# connector_a.net
KiCad netlist of a schematic drawn in Altium Designer
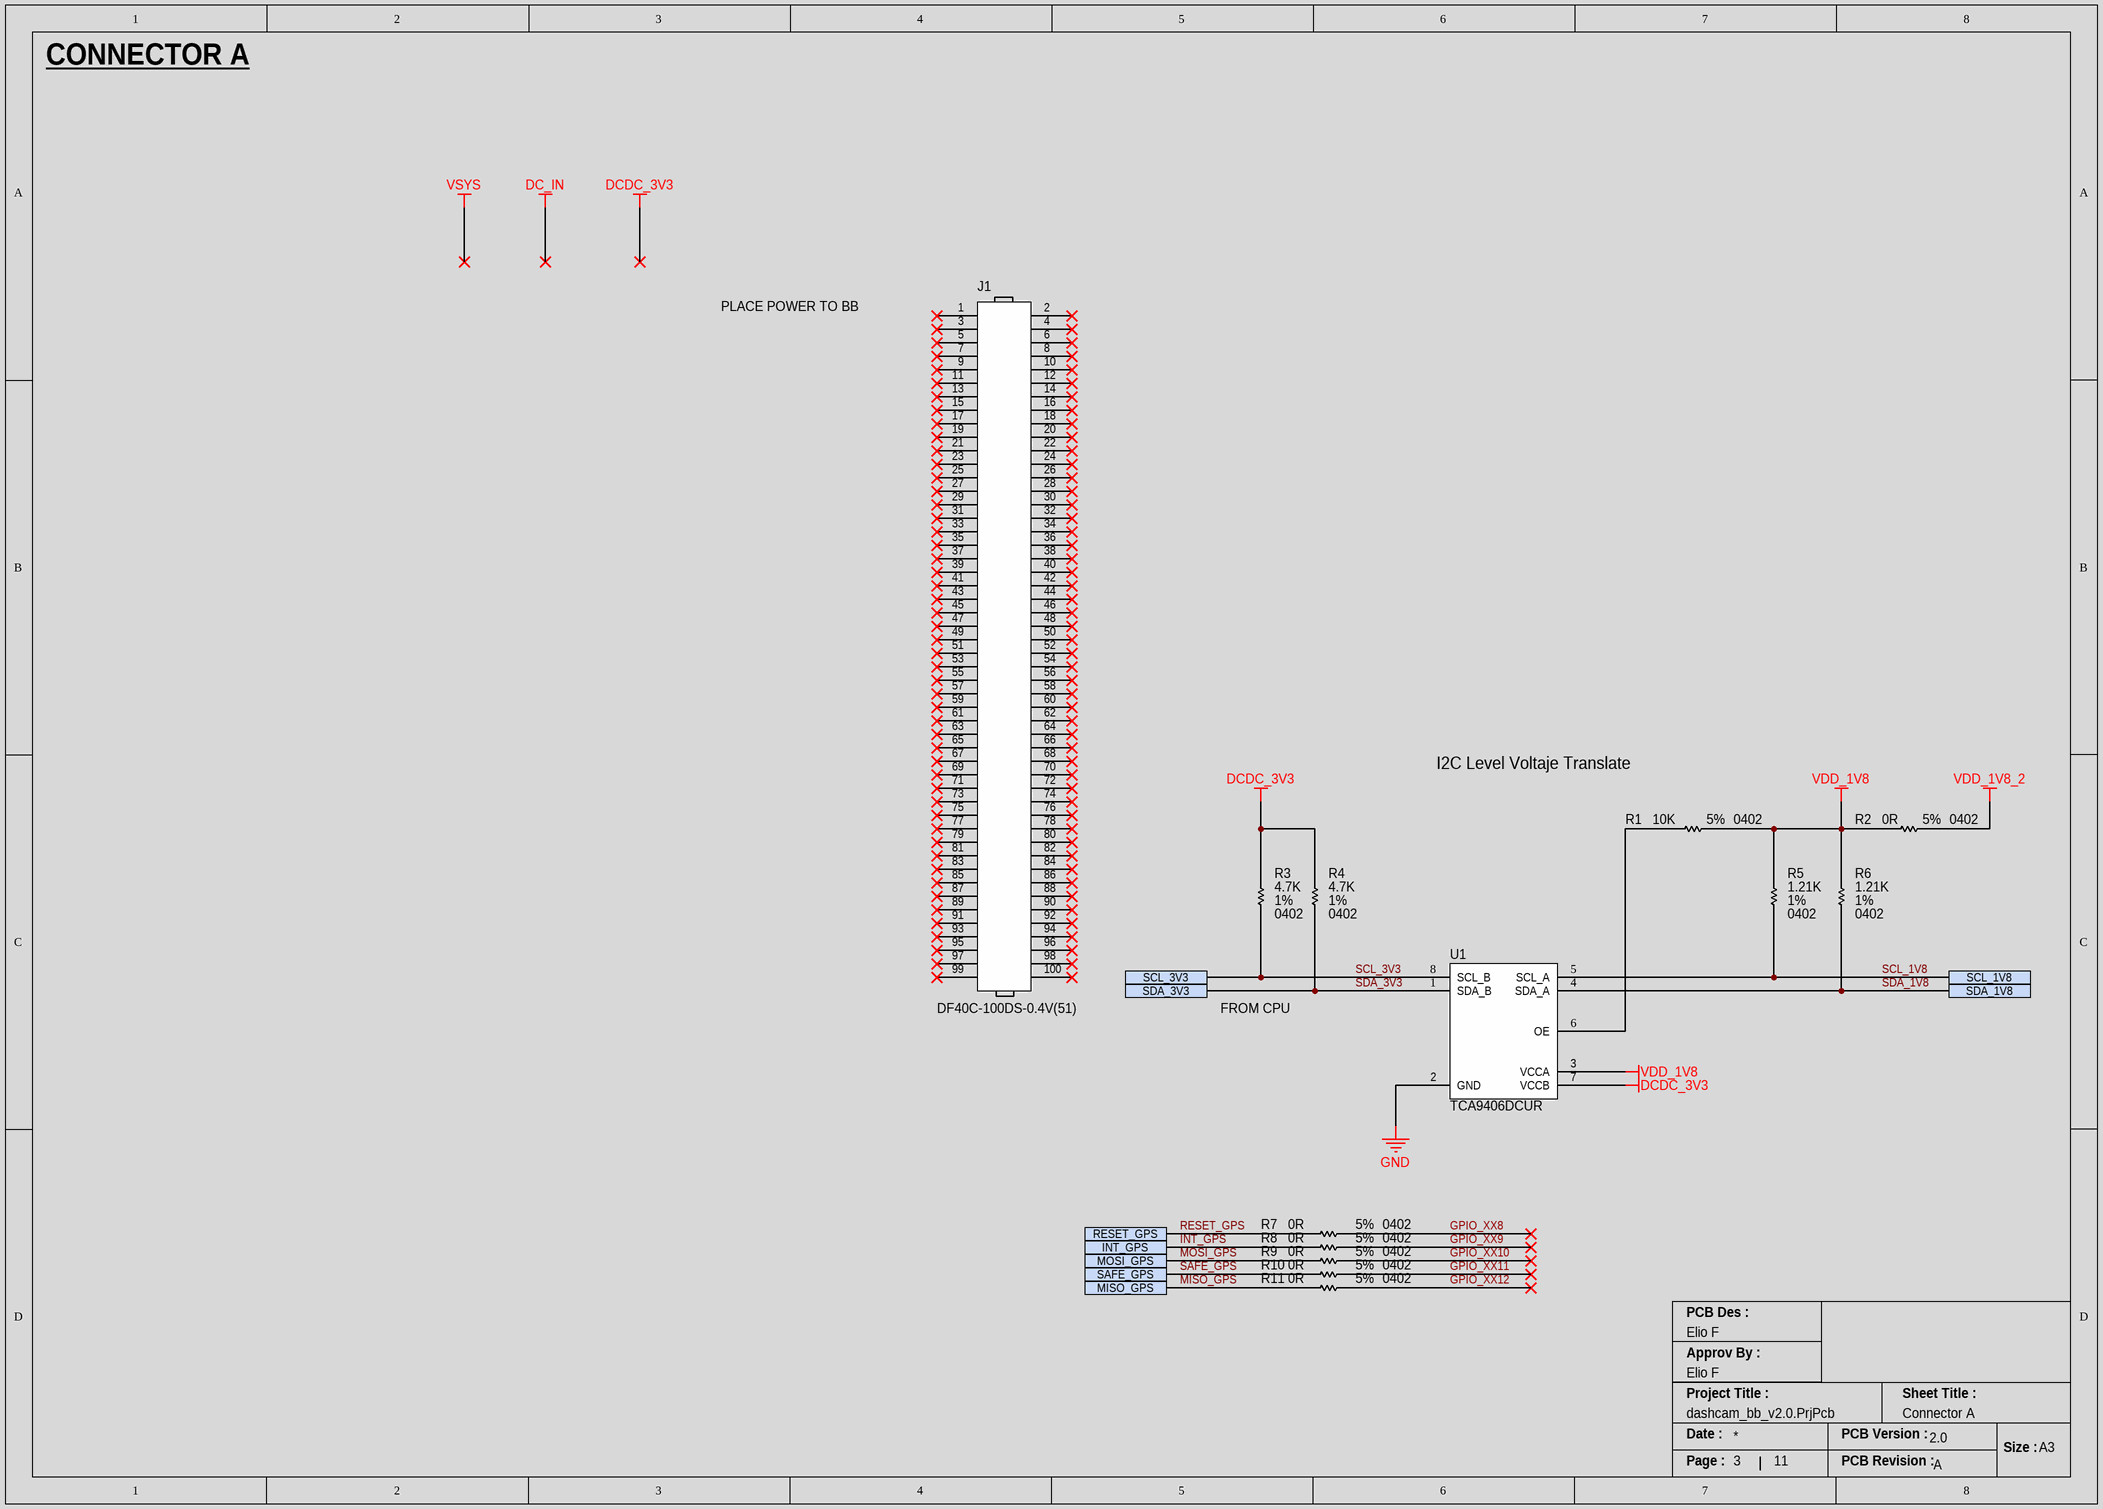
[diagram p0: connector_a.SchDoc]

(export (version "E")
  (design (tool "Eeschema 10.0.6"))
  (components
    (comp (ref "J1")
      (value "DF40C-100DS-0.4V(51)")
      (footprint "CONN_B2B_HIROSE_DF40C-100DS-0.4V(51)")
      (description "Board-to-Board Connector with 0.4-mm Pitch, 1.5 - 4.0-mm Height - DF40 Series (HIROSE ELECTRIC)")
      (fields (field (name "MANUFACTURER") "Hirose"))
      (libsource (lib "Electronic Devices_LIB") (part "CONN_B2B_100P_RE_DF40C-100DS-0.4V(51)"))
    )
    (comp (ref "R1")
      (value "ERJ-2GEJ103X")
      (footprint "RES_0402_RESC1005X04N")
      (description "Res Thick Film 0402 10K Ohm 5% 1/10W ±200ppm/°C Molded SMD Punched Carrier T/R")
      (fields
        (field (name "MANUFACTURER") "Panasonic")
        (field (name "TOLERANCE") "5%")
        (field (name "RESISTANCE") "10K")
        (field (name "CASE/PACKAGE") "0402")
      )
      (libsource (lib "Electronic Devices_LIB") (part "RES_10K_5%_100mW_0402"))
    )
    (comp (ref "R2")
      (value "ERJ-2GE0R00X")
      (footprint "RES_0402_RESC1005X04N")
      (description "SMD Chip Resistor, Jumper, 0 ohm, 100 mW, 0402 [1005 Metric], Thick Film, General Purpose")
      (fields
        (field (name "MANUFACTURER") "Panasonic")
        (field (name "CASE CODE (IMPERIAL)") "0402")
        (field (name "TOLERANCE") "5%")
        (field (name "RESISTANCE") "0R")
      )
      (libsource (lib "Electronic Devices_LIB") (part "RES_0R_5%_100mW_0402"))
    )
    (comp (ref "R3")
      (value "ERJ-2RKF4701X")
      (footprint "RES_0402_RESC1005X04N")
      (description "Res Thick Film 0402 4.7K Ohm 1% 0.1W ±100ppm/°C Molded SMD Punched Carrier T/R")
      (fields
        (field (name "MANUFACTURER") "Panasonic")
        (field (name "TOLERANCE") "1%")
        (field (name "CASE CODE (IMPERIAL)") "0402")
        (field (name "RESISTANCE") "4.7K")
      )
      (libsource (lib "Electronic Devices_LIB") (part "RES_4.7K_1%_100mW_0402"))
    )
    (comp (ref "R4")
      (value "ERJ-2RKF4701X")
      (footprint "RES_0402_RESC1005X04N")
      (description "Res Thick Film 0402 4.7K Ohm 1% 0.1W ±100ppm/°C Molded SMD Punched Carrier T/R")
      (fields
        (field (name "MANUFACTURER") "Panasonic")
        (field (name "TOLERANCE") "1%")
        (field (name "CASE CODE (IMPERIAL)") "0402")
        (field (name "RESISTANCE") "4.7K")
      )
      (libsource (lib "Electronic Devices_LIB") (part "RES_4.7K_1%_100mW_0402"))
    )
    (comp (ref "R5")
      (value "CRCW04021K21FKED")
      (footprint "RES_0402_RESC1005X04N")
      (description "Res Thick Film 0402 1.21K Ohm 1% 1/16W ±100ppm/°C Molded SMD Paper T/R")
      (fields
        (field (name "MANUFACTURER") "Vishay")
        (field (name "TOLERANCE") "1%")
        (field (name "RESISTANCE") "1.21K")
        (field (name "CASE/PACKAGE") "0402")
      )
      (libsource (lib "Electronic Devices_LIB") (part "RES_1.21K_1%_63mW_0402"))
    )
    (comp (ref "R6")
      (value "CRCW04021K21FKED")
      (footprint "RES_0402_RESC1005X04N")
      (description "Res Thick Film 0402 1.21K Ohm 1% 1/16W ±100ppm/°C Molded SMD Paper T/R")
      (fields
        (field (name "MANUFACTURER") "Vishay")
        (field (name "TOLERANCE") "1%")
        (field (name "RESISTANCE") "1.21K")
        (field (name "CASE/PACKAGE") "0402")
      )
      (libsource (lib "Electronic Devices_LIB") (part "RES_1.21K_1%_63mW_0402"))
    )
    (comp (ref "R7")
      (value "ERJ-2GE0R00X")
      (footprint "RES_0402_RESC1005X04N")
      (description "SMD Chip Resistor, Jumper, 0 ohm, 100 mW, 0402 [1005 Metric], Thick Film, General Purpose")
      (fields
        (field (name "MANUFACTURER") "Panasonic")
        (field (name "CASE CODE (IMPERIAL)") "0402")
        (field (name "TOLERANCE") "5%")
        (field (name "RESISTANCE") "0R")
      )
      (libsource (lib "Electronic Devices_LIB") (part "RES_0R_5%_100mW_0402"))
    )
    (comp (ref "R8")
      (value "ERJ-2GE0R00X")
      (footprint "RES_0402_RESC1005X04N")
      (description "SMD Chip Resistor, Jumper, 0 ohm, 100 mW, 0402 [1005 Metric], Thick Film, General Purpose")
      (fields
        (field (name "MANUFACTURER") "Panasonic")
        (field (name "CASE CODE (IMPERIAL)") "0402")
        (field (name "TOLERANCE") "5%")
        (field (name "RESISTANCE") "0R")
      )
      (libsource (lib "Electronic Devices_LIB") (part "RES_0R_5%_100mW_0402"))
    )
    (comp (ref "R9")
      (value "ERJ-2GE0R00X")
      (footprint "RES_0402_RESC1005X04N")
      (description "SMD Chip Resistor, Jumper, 0 ohm, 100 mW, 0402 [1005 Metric], Thick Film, General Purpose")
      (fields
        (field (name "MANUFACTURER") "Panasonic")
        (field (name "CASE CODE (IMPERIAL)") "0402")
        (field (name "TOLERANCE") "5%")
        (field (name "RESISTANCE") "0R")
      )
      (libsource (lib "Electronic Devices_LIB") (part "RES_0R_5%_100mW_0402"))
    )
    (comp (ref "R10")
      (value "ERJ-2GE0R00X")
      (footprint "RES_0402_RESC1005X04N")
      (description "SMD Chip Resistor, Jumper, 0 ohm, 100 mW, 0402 [1005 Metric], Thick Film, General Purpose")
      (fields
        (field (name "MANUFACTURER") "Panasonic")
        (field (name "CASE CODE (IMPERIAL)") "0402")
        (field (name "TOLERANCE") "5%")
        (field (name "RESISTANCE") "0R")
      )
      (libsource (lib "Electronic Devices_LIB") (part "RES_0R_5%_100mW_0402"))
    )
    (comp (ref "R11")
      (value "ERJ-2GE0R00X")
      (footprint "RES_0402_RESC1005X04N")
      (description "SMD Chip Resistor, Jumper, 0 ohm, 100 mW, 0402 [1005 Metric], Thick Film, General Purpose")
      (fields
        (field (name "MANUFACTURER") "Panasonic")
        (field (name "CASE CODE (IMPERIAL)") "0402")
        (field (name "TOLERANCE") "5%")
        (field (name "RESISTANCE") "0R")
      )
      (libsource (lib "Electronic Devices_LIB") (part "RES_0R_5%_100mW_0402"))
    )
    (comp (ref "U1")
      (value "TCA9406DCUR")
      (footprint "IC_LEVEL_TRASLATOR_SOP50P310X90-8N")
      (description "Voltage Level Translator Bidirectional 1 Circuit 2 Channel 24Mbps US8")
      (fields (field (name "MANUFACTURER") "Texas Instruments"))
      (libsource (lib "Electronic Devices_LIB") (part "IC_LEVEL_TRASLATOR_TCA9406DCUR"))
    )
  )
  (nets
    (net (code "1") (name "/GPIO_XX8") (class "Default")
      (node (ref "R7") (pin "2") (pinfunction "2_2") (pintype "passive+no_connect"))
    )
    (net (code "2") (name "/GPIO_XX9") (class "Default")
      (node (ref "R8") (pin "2") (pinfunction "2_2") (pintype "passive+no_connect"))
    )
    (net (code "3") (name "/GPIO_XX10") (class "Default")
      (node (ref "R9") (pin "2") (pinfunction "2_2") (pintype "passive+no_connect"))
    )
    (net (code "4") (name "/GPIO_XX11") (class "Default")
      (node (ref "R10") (pin "2") (pinfunction "2_2") (pintype "passive+no_connect"))
    )
    (net (code "5") (name "/GPIO_XX12") (class "Default")
      (node (ref "R11") (pin "2") (pinfunction "2_2") (pintype "passive+no_connect"))
    )
    (net (code "6") (name "/INT_GPS") (class "Default")
      (node (ref "R8") (pin "1") (pinfunction "1_1") (pintype "passive"))
    )
    (net (code "7") (name "/MISO_GPS") (class "Default")
      (node (ref "R11") (pin "1") (pinfunction "1_1") (pintype "passive"))
    )
    (net (code "8") (name "/MOSI_GPS") (class "Default")
      (node (ref "R9") (pin "1") (pinfunction "1_1") (pintype "passive"))
    )
    (net (code "9") (name "/RESET_GPS") (class "Default")
      (node (ref "R7") (pin "1") (pinfunction "1_1") (pintype "passive"))
    )
    (net (code "10") (name "/SAFE_GPS") (class "Default")
      (node (ref "R10") (pin "1") (pinfunction "1_1") (pintype "passive"))
    )
    (net (code "11") (name "/SCL_1V8") (class "Default")
      (node (ref "R5") (pin "1") (pinfunction "1_1") (pintype "passive"))
      (node (ref "U1") (pin "5") (pinfunction "SCL_A_5") (pintype "passive"))
    )
    (net (code "12") (name "/SCL_3V3") (class "Default")
      (node (ref "R3") (pin "2") (pinfunction "2_2") (pintype "passive"))
      (node (ref "U1") (pin "8") (pinfunction "SCL_B_8") (pintype "passive"))
    )
    (net (code "13") (name "/SDA_1V8") (class "Default")
      (node (ref "R6") (pin "1") (pinfunction "1_1") (pintype "passive"))
      (node (ref "U1") (pin "4") (pinfunction "SDA_A_4") (pintype "passive"))
    )
    (net (code "14") (name "/SDA_3V3") (class "Default")
      (node (ref "R4") (pin "2") (pinfunction "2_2") (pintype "passive"))
      (node (ref "U1") (pin "1") (pinfunction "SDA_B_1") (pintype "passive"))
    )
    (net (code "15") (name "DCDC_3V3") (class "Default")
      (node (ref "R3") (pin "1") (pinfunction "1_1") (pintype "passive"))
      (node (ref "R4") (pin "1") (pinfunction "1_1") (pintype "passive"))
      (node (ref "U1") (pin "7") (pinfunction "VCCB_7") (pintype "power_in"))
    )
    (net (code "17") (name "GND") (class "Default")
      (node (ref "U1") (pin "2") (pinfunction "GND_2") (pintype "power_in"))
    )
    (net (code "18") (name "Net-(U1-OE)") (class "Default")
      (node (ref "R1") (pin "1") (pinfunction "1_1") (pintype "passive"))
      (node (ref "U1") (pin "6") (pinfunction "OE_6") (pintype "passive"))
    )
    (net (code "19") (name "VDD_1V8") (class "Default")
      (node (ref "R1") (pin "2") (pinfunction "2_2") (pintype "passive"))
      (node (ref "R2") (pin "1") (pinfunction "1_1") (pintype "passive"))
      (node (ref "R5") (pin "2") (pinfunction "2_2") (pintype "passive"))
      (node (ref "R6") (pin "2") (pinfunction "2_2") (pintype "passive"))
      (node (ref "U1") (pin "3") (pinfunction "VCCA_3") (pintype "power_in"))
    )
    (net (code "20") (name "VDD_1V8_2") (class "Default")
      (node (ref "R2") (pin "2") (pinfunction "2_2") (pintype "passive"))
    )
    (net (code "22") (name "unconnected-(J1-Pad1)") (class "Default")
      (node (ref "J1") (pin "1") (pinfunction "1_1") (pintype "passive+no_connect"))
    )
    (net (code "23") (name "unconnected-(J1-Pad2)") (class "Default")
      (node (ref "J1") (pin "2") (pinfunction "2_2") (pintype "passive+no_connect"))
    )
    (net (code "24") (name "unconnected-(J1-Pad3)") (class "Default")
      (node (ref "J1") (pin "3") (pinfunction "3_3") (pintype "passive+no_connect"))
    )
    (net (code "25") (name "unconnected-(J1-Pad4)") (class "Default")
      (node (ref "J1") (pin "4") (pinfunction "4_4") (pintype "passive+no_connect"))
    )
    (net (code "26") (name "unconnected-(J1-Pad5)") (class "Default")
      (node (ref "J1") (pin "5") (pinfunction "5_5") (pintype "passive+no_connect"))
    )
    (net (code "27") (name "unconnected-(J1-Pad6)") (class "Default")
      (node (ref "J1") (pin "6") (pinfunction "6_6") (pintype "passive+no_connect"))
    )
    (net (code "28") (name "unconnected-(J1-Pad7)") (class "Default")
      (node (ref "J1") (pin "7") (pinfunction "7_7") (pintype "passive+no_connect"))
    )
    (net (code "29") (name "unconnected-(J1-Pad8)") (class "Default")
      (node (ref "J1") (pin "8") (pinfunction "8_8") (pintype "passive+no_connect"))
    )
    (net (code "30") (name "unconnected-(J1-Pad9)") (class "Default")
      (node (ref "J1") (pin "9") (pinfunction "9_9") (pintype "passive+no_connect"))
    )
    (net (code "31") (name "unconnected-(J1-Pad10)") (class "Default")
      (node (ref "J1") (pin "10") (pinfunction "10_10") (pintype "passive+no_connect"))
    )
    (net (code "32") (name "unconnected-(J1-Pad11)") (class "Default")
      (node (ref "J1") (pin "11") (pinfunction "11_11") (pintype "passive+no_connect"))
    )
    (net (code "33") (name "unconnected-(J1-Pad12)") (class "Default")
      (node (ref "J1") (pin "12") (pinfunction "12_12") (pintype "passive+no_connect"))
    )
    (net (code "34") (name "unconnected-(J1-Pad13)") (class "Default")
      (node (ref "J1") (pin "13") (pinfunction "13_13") (pintype "passive+no_connect"))
    )
    (net (code "35") (name "unconnected-(J1-Pad14)") (class "Default")
      (node (ref "J1") (pin "14") (pinfunction "14_14") (pintype "passive+no_connect"))
    )
    (net (code "36") (name "unconnected-(J1-Pad15)") (class "Default")
      (node (ref "J1") (pin "15") (pinfunction "15_15") (pintype "passive+no_connect"))
    )
    (net (code "37") (name "unconnected-(J1-Pad16)") (class "Default")
      (node (ref "J1") (pin "16") (pinfunction "16_16") (pintype "passive+no_connect"))
    )
    (net (code "38") (name "unconnected-(J1-Pad17)") (class "Default")
      (node (ref "J1") (pin "17") (pinfunction "17_17") (pintype "passive+no_connect"))
    )
    (net (code "39") (name "unconnected-(J1-Pad18)") (class "Default")
      (node (ref "J1") (pin "18") (pinfunction "18_18") (pintype "passive+no_connect"))
    )
    (net (code "40") (name "unconnected-(J1-Pad19)") (class "Default")
      (node (ref "J1") (pin "19") (pinfunction "19_19") (pintype "passive+no_connect"))
    )
    (net (code "41") (name "unconnected-(J1-Pad20)") (class "Default")
      (node (ref "J1") (pin "20") (pinfunction "20_20") (pintype "passive+no_connect"))
    )
    (net (code "42") (name "unconnected-(J1-Pad21)") (class "Default")
      (node (ref "J1") (pin "21") (pinfunction "21_21") (pintype "passive+no_connect"))
    )
    (net (code "43") (name "unconnected-(J1-Pad22)") (class "Default")
      (node (ref "J1") (pin "22") (pinfunction "22_22") (pintype "passive+no_connect"))
    )
    (net (code "44") (name "unconnected-(J1-Pad23)") (class "Default")
      (node (ref "J1") (pin "23") (pinfunction "23_23") (pintype "passive+no_connect"))
    )
    (net (code "45") (name "unconnected-(J1-Pad24)") (class "Default")
      (node (ref "J1") (pin "24") (pinfunction "24_24") (pintype "passive+no_connect"))
    )
    (net (code "46") (name "unconnected-(J1-Pad25)") (class "Default")
      (node (ref "J1") (pin "25") (pinfunction "25_25") (pintype "passive+no_connect"))
    )
    (net (code "47") (name "unconnected-(J1-Pad26)") (class "Default")
      (node (ref "J1") (pin "26") (pinfunction "26_26") (pintype "passive+no_connect"))
    )
    (net (code "48") (name "unconnected-(J1-Pad27)") (class "Default")
      (node (ref "J1") (pin "27") (pinfunction "27_27") (pintype "passive+no_connect"))
    )
    (net (code "49") (name "unconnected-(J1-Pad28)") (class "Default")
      (node (ref "J1") (pin "28") (pinfunction "28_28") (pintype "passive+no_connect"))
    )
    (net (code "50") (name "unconnected-(J1-Pad29)") (class "Default")
      (node (ref "J1") (pin "29") (pinfunction "29_29") (pintype "passive+no_connect"))
    )
    (net (code "51") (name "unconnected-(J1-Pad30)") (class "Default")
      (node (ref "J1") (pin "30") (pinfunction "30_30") (pintype "passive+no_connect"))
    )
    (net (code "52") (name "unconnected-(J1-Pad31)") (class "Default")
      (node (ref "J1") (pin "31") (pinfunction "31_31") (pintype "passive+no_connect"))
    )
    (net (code "53") (name "unconnected-(J1-Pad32)") (class "Default")
      (node (ref "J1") (pin "32") (pinfunction "32_32") (pintype "passive+no_connect"))
    )
    (net (code "54") (name "unconnected-(J1-Pad33)") (class "Default")
      (node (ref "J1") (pin "33") (pinfunction "33_33") (pintype "passive+no_connect"))
    )
    (net (code "55") (name "unconnected-(J1-Pad34)") (class "Default")
      (node (ref "J1") (pin "34") (pinfunction "34_34") (pintype "passive+no_connect"))
    )
    (net (code "56") (name "unconnected-(J1-Pad35)") (class "Default")
      (node (ref "J1") (pin "35") (pinfunction "35_35") (pintype "passive+no_connect"))
    )
    (net (code "57") (name "unconnected-(J1-Pad36)") (class "Default")
      (node (ref "J1") (pin "36") (pinfunction "36_36") (pintype "passive+no_connect"))
    )
    (net (code "58") (name "unconnected-(J1-Pad37)") (class "Default")
      (node (ref "J1") (pin "37") (pinfunction "37_37") (pintype "passive+no_connect"))
    )
    (net (code "59") (name "unconnected-(J1-Pad38)") (class "Default")
      (node (ref "J1") (pin "38") (pinfunction "38_38") (pintype "passive+no_connect"))
    )
    (net (code "60") (name "unconnected-(J1-Pad39)") (class "Default")
      (node (ref "J1") (pin "39") (pinfunction "39_39") (pintype "passive+no_connect"))
    )
    (net (code "61") (name "unconnected-(J1-Pad40)") (class "Default")
      (node (ref "J1") (pin "40") (pinfunction "40_40") (pintype "passive+no_connect"))
    )
    (net (code "62") (name "unconnected-(J1-Pad41)") (class "Default")
      (node (ref "J1") (pin "41") (pinfunction "41_41") (pintype "passive+no_connect"))
    )
    (net (code "63") (name "unconnected-(J1-Pad42)") (class "Default")
      (node (ref "J1") (pin "42") (pinfunction "42_42") (pintype "passive+no_connect"))
    )
    (net (code "64") (name "unconnected-(J1-Pad43)") (class "Default")
      (node (ref "J1") (pin "43") (pinfunction "43_43") (pintype "passive+no_connect"))
    )
    (net (code "65") (name "unconnected-(J1-Pad44)") (class "Default")
      (node (ref "J1") (pin "44") (pinfunction "44_44") (pintype "passive+no_connect"))
    )
    (net (code "66") (name "unconnected-(J1-Pad45)") (class "Default")
      (node (ref "J1") (pin "45") (pinfunction "45_45") (pintype "passive+no_connect"))
    )
    (net (code "67") (name "unconnected-(J1-Pad46)") (class "Default")
      (node (ref "J1") (pin "46") (pinfunction "46_46") (pintype "passive+no_connect"))
    )
    (net (code "68") (name "unconnected-(J1-Pad47)") (class "Default")
      (node (ref "J1") (pin "47") (pinfunction "47_47") (pintype "passive+no_connect"))
    )
    (net (code "69") (name "unconnected-(J1-Pad48)") (class "Default")
      (node (ref "J1") (pin "48") (pinfunction "48_48") (pintype "passive+no_connect"))
    )
    (net (code "70") (name "unconnected-(J1-Pad49)") (class "Default")
      (node (ref "J1") (pin "49") (pinfunction "49_49") (pintype "passive+no_connect"))
    )
    (net (code "71") (name "unconnected-(J1-Pad50)") (class "Default")
      (node (ref "J1") (pin "50") (pinfunction "50_50") (pintype "passive+no_connect"))
    )
    (net (code "72") (name "unconnected-(J1-Pad51)") (class "Default")
      (node (ref "J1") (pin "51") (pinfunction "51_51") (pintype "passive+no_connect"))
    )
    (net (code "73") (name "unconnected-(J1-Pad52)") (class "Default")
      (node (ref "J1") (pin "52") (pinfunction "52_52") (pintype "passive+no_connect"))
    )
    (net (code "74") (name "unconnected-(J1-Pad53)") (class "Default")
      (node (ref "J1") (pin "53") (pinfunction "53_53") (pintype "passive+no_connect"))
    )
    (net (code "75") (name "unconnected-(J1-Pad54)") (class "Default")
      (node (ref "J1") (pin "54") (pinfunction "54_54") (pintype "passive+no_connect"))
    )
    (net (code "76") (name "unconnected-(J1-Pad55)") (class "Default")
      (node (ref "J1") (pin "55") (pinfunction "55_55") (pintype "passive+no_connect"))
    )
    (net (code "77") (name "unconnected-(J1-Pad56)") (class "Default")
      (node (ref "J1") (pin "56") (pinfunction "56_56") (pintype "passive+no_connect"))
    )
    (net (code "78") (name "unconnected-(J1-Pad57)") (class "Default")
      (node (ref "J1") (pin "57") (pinfunction "57_57") (pintype "passive+no_connect"))
    )
    (net (code "79") (name "unconnected-(J1-Pad58)") (class "Default")
      (node (ref "J1") (pin "58") (pinfunction "58_58") (pintype "passive+no_connect"))
    )
    (net (code "80") (name "unconnected-(J1-Pad59)") (class "Default")
      (node (ref "J1") (pin "59") (pinfunction "59_59") (pintype "passive+no_connect"))
    )
    (net (code "81") (name "unconnected-(J1-Pad60)") (class "Default")
      (node (ref "J1") (pin "60") (pinfunction "60_60") (pintype "passive+no_connect"))
    )
    (net (code "82") (name "unconnected-(J1-Pad61)") (class "Default")
      (node (ref "J1") (pin "61") (pinfunction "61_61") (pintype "passive+no_connect"))
    )
    (net (code "83") (name "unconnected-(J1-Pad62)") (class "Default")
      (node (ref "J1") (pin "62") (pinfunction "62_62") (pintype "passive+no_connect"))
    )
    (net (code "84") (name "unconnected-(J1-Pad63)") (class "Default")
      (node (ref "J1") (pin "63") (pinfunction "63_63") (pintype "passive+no_connect"))
    )
    (net (code "85") (name "unconnected-(J1-Pad64)") (class "Default")
      (node (ref "J1") (pin "64") (pinfunction "64_64") (pintype "passive+no_connect"))
    )
    (net (code "86") (name "unconnected-(J1-Pad65)") (class "Default")
      (node (ref "J1") (pin "65") (pinfunction "65_65") (pintype "passive+no_connect"))
    )
    (net (code "87") (name "unconnected-(J1-Pad66)") (class "Default")
      (node (ref "J1") (pin "66") (pinfunction "66_66") (pintype "passive+no_connect"))
    )
    (net (code "88") (name "unconnected-(J1-Pad67)") (class "Default")
      (node (ref "J1") (pin "67") (pinfunction "67_67") (pintype "passive+no_connect"))
    )
    (net (code "89") (name "unconnected-(J1-Pad68)") (class "Default")
      (node (ref "J1") (pin "68") (pinfunction "68_68") (pintype "passive+no_connect"))
    )
    (net (code "90") (name "unconnected-(J1-Pad69)") (class "Default")
      (node (ref "J1") (pin "69") (pinfunction "69_69") (pintype "passive+no_connect"))
    )
    (net (code "91") (name "unconnected-(J1-Pad70)") (class "Default")
      (node (ref "J1") (pin "70") (pinfunction "70_70") (pintype "passive+no_connect"))
    )
    (net (code "92") (name "unconnected-(J1-Pad71)") (class "Default")
      (node (ref "J1") (pin "71") (pinfunction "71_71") (pintype "passive+no_connect"))
    )
    (net (code "93") (name "unconnected-(J1-Pad72)") (class "Default")
      (node (ref "J1") (pin "72") (pinfunction "72_72") (pintype "passive+no_connect"))
    )
    (net (code "94") (name "unconnected-(J1-Pad73)") (class "Default")
      (node (ref "J1") (pin "73") (pinfunction "73_73") (pintype "passive+no_connect"))
    )
    (net (code "95") (name "unconnected-(J1-Pad74)") (class "Default")
      (node (ref "J1") (pin "74") (pinfunction "74_74") (pintype "passive+no_connect"))
    )
    (net (code "96") (name "unconnected-(J1-Pad75)") (class "Default")
      (node (ref "J1") (pin "75") (pinfunction "75_75") (pintype "passive+no_connect"))
    )
    (net (code "97") (name "unconnected-(J1-Pad76)") (class "Default")
      (node (ref "J1") (pin "76") (pinfunction "76_76") (pintype "passive+no_connect"))
    )
    (net (code "98") (name "unconnected-(J1-Pad77)") (class "Default")
      (node (ref "J1") (pin "77") (pinfunction "77_77") (pintype "passive+no_connect"))
    )
    (net (code "99") (name "unconnected-(J1-Pad78)") (class "Default")
      (node (ref "J1") (pin "78") (pinfunction "78_78") (pintype "passive+no_connect"))
    )
    (net (code "100") (name "unconnected-(J1-Pad79)") (class "Default")
      (node (ref "J1") (pin "79") (pinfunction "79_79") (pintype "passive+no_connect"))
    )
    (net (code "101") (name "unconnected-(J1-Pad80)") (class "Default")
      (node (ref "J1") (pin "80") (pinfunction "80_80") (pintype "passive+no_connect"))
    )
    (net (code "102") (name "unconnected-(J1-Pad81)") (class "Default")
      (node (ref "J1") (pin "81") (pinfunction "81_81") (pintype "passive+no_connect"))
    )
    (net (code "103") (name "unconnected-(J1-Pad82)") (class "Default")
      (node (ref "J1") (pin "82") (pinfunction "82_82") (pintype "passive+no_connect"))
    )
    (net (code "104") (name "unconnected-(J1-Pad83)") (class "Default")
      (node (ref "J1") (pin "83") (pinfunction "83_83") (pintype "passive+no_connect"))
    )
    (net (code "105") (name "unconnected-(J1-Pad84)") (class "Default")
      (node (ref "J1") (pin "84") (pinfunction "84_84") (pintype "passive+no_connect"))
    )
    (net (code "106") (name "unconnected-(J1-Pad85)") (class "Default")
      (node (ref "J1") (pin "85") (pinfunction "85_85") (pintype "passive+no_connect"))
    )
    (net (code "107") (name "unconnected-(J1-Pad86)") (class "Default")
      (node (ref "J1") (pin "86") (pinfunction "86_86") (pintype "passive+no_connect"))
    )
    (net (code "108") (name "unconnected-(J1-Pad87)") (class "Default")
      (node (ref "J1") (pin "87") (pinfunction "87_87") (pintype "passive+no_connect"))
    )
    (net (code "109") (name "unconnected-(J1-Pad88)") (class "Default")
      (node (ref "J1") (pin "88") (pinfunction "88_88") (pintype "passive+no_connect"))
    )
    (net (code "110") (name "unconnected-(J1-Pad89)") (class "Default")
      (node (ref "J1") (pin "89") (pinfunction "89_89") (pintype "passive+no_connect"))
    )
    (net (code "111") (name "unconnected-(J1-Pad90)") (class "Default")
      (node (ref "J1") (pin "90") (pinfunction "90_90") (pintype "passive+no_connect"))
    )
    (net (code "112") (name "unconnected-(J1-Pad91)") (class "Default")
      (node (ref "J1") (pin "91") (pinfunction "91_91") (pintype "passive+no_connect"))
    )
    (net (code "113") (name "unconnected-(J1-Pad92)") (class "Default")
      (node (ref "J1") (pin "92") (pinfunction "92_92") (pintype "passive+no_connect"))
    )
    (net (code "114") (name "unconnected-(J1-Pad93)") (class "Default")
      (node (ref "J1") (pin "93") (pinfunction "93_93") (pintype "passive+no_connect"))
    )
    (net (code "115") (name "unconnected-(J1-Pad94)") (class "Default")
      (node (ref "J1") (pin "94") (pinfunction "94_94") (pintype "passive+no_connect"))
    )
    (net (code "116") (name "unconnected-(J1-Pad95)") (class "Default")
      (node (ref "J1") (pin "95") (pinfunction "95_95") (pintype "passive+no_connect"))
    )
    (net (code "117") (name "unconnected-(J1-Pad96)") (class "Default")
      (node (ref "J1") (pin "96") (pinfunction "96_96") (pintype "passive+no_connect"))
    )
    (net (code "118") (name "unconnected-(J1-Pad97)") (class "Default")
      (node (ref "J1") (pin "97") (pinfunction "97_97") (pintype "passive+no_connect"))
    )
    (net (code "119") (name "unconnected-(J1-Pad98)") (class "Default")
      (node (ref "J1") (pin "98") (pinfunction "98_98") (pintype "passive+no_connect"))
    )
    (net (code "120") (name "unconnected-(J1-Pad99)") (class "Default")
      (node (ref "J1") (pin "99") (pinfunction "99_99") (pintype "passive+no_connect"))
    )
    (net (code "121") (name "unconnected-(J1-Pad100)") (class "Default")
      (node (ref "J1") (pin "100") (pinfunction "100_100") (pintype "passive+no_connect"))
    )
  )
)
